# elflet.net
KiCad netlist of a schematic drawn in EAGLE
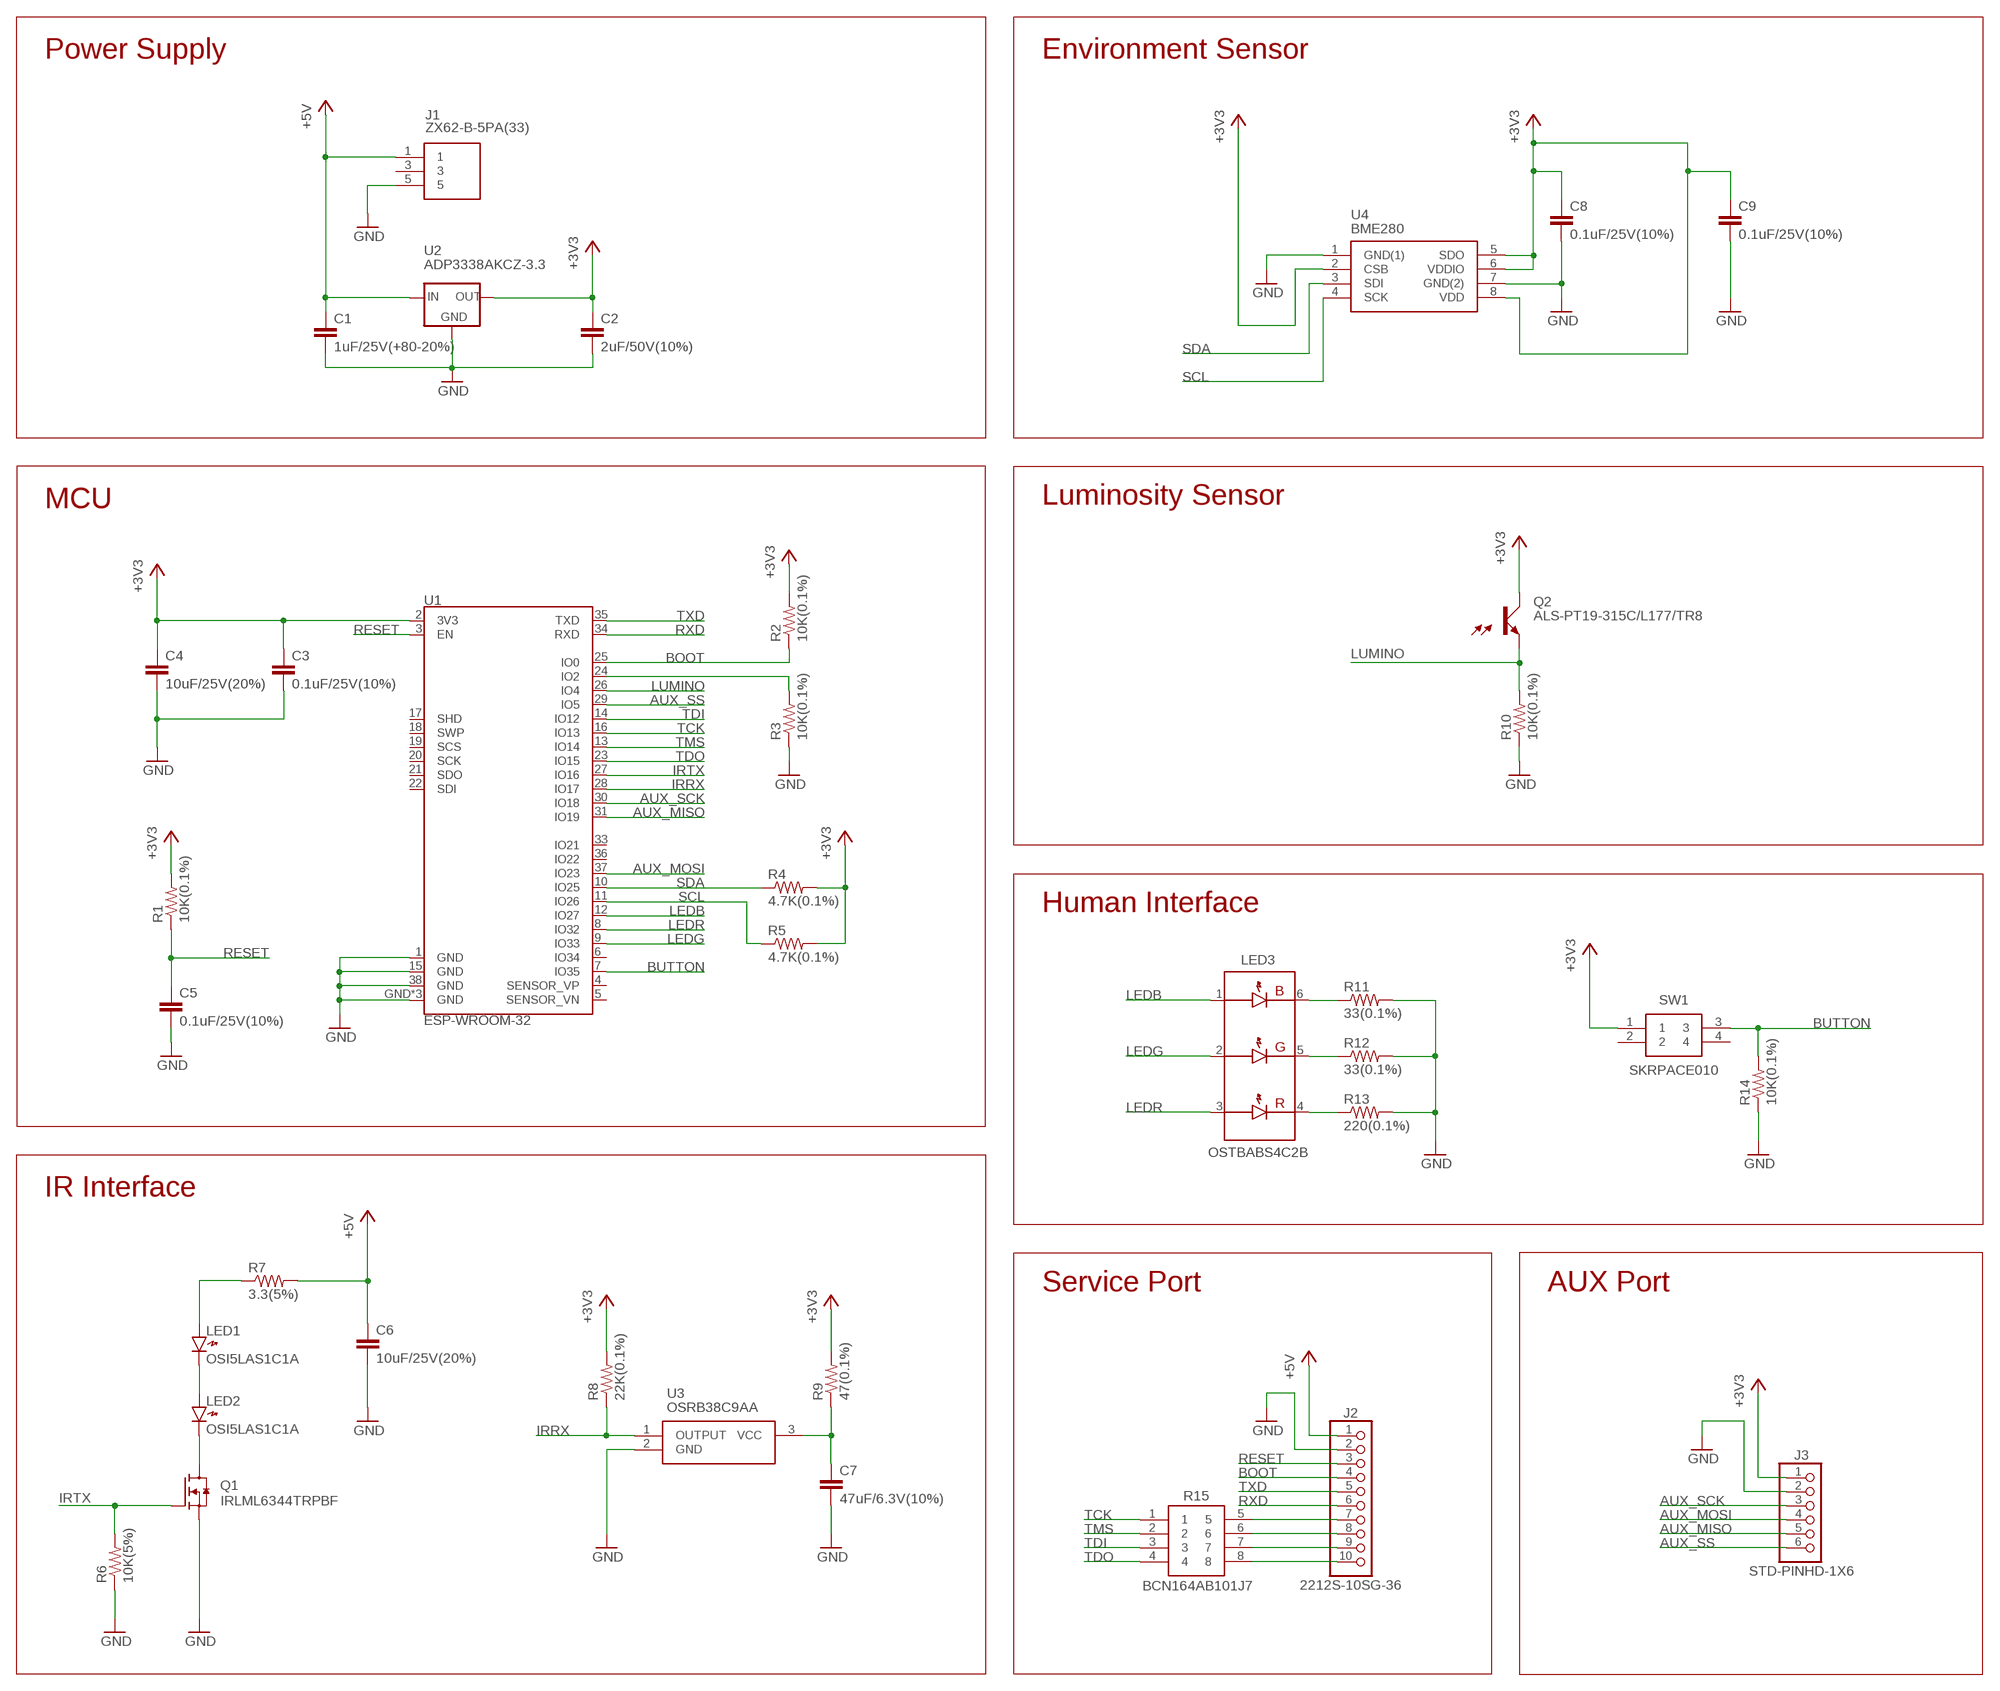
[diagram p0: schematic, sheet 1]

(export (version "E")
  (design (tool "Eeschema 10.0.6"))
  (components
    (comp (ref "C1")
      (value "1uF/25V(+80-20%)")
      (footprint "eagle-import:C3216")
      (libsource (lib "eagle-import") (part "C-EUC3216"))
    )
    (comp (ref "C2")
      (value "2uF/50V(10%)")
      (footprint "eagle-import:C3216")
      (libsource (lib "eagle-import") (part "C-EUC3216"))
    )
    (comp (ref "C3")
      (value "0.1uF/25V(10%)")
      (footprint "eagle-import:C1608")
      (libsource (lib "eagle-import") (part "C-EUC1608"))
    )
    (comp (ref "C4")
      (value "10uF/25V(20%)")
      (footprint "eagle-import:C1608")
      (libsource (lib "eagle-import") (part "C-EUC1608"))
    )
    (comp (ref "C5")
      (value "0.1uF/25V(10%)")
      (footprint "eagle-import:C1608")
      (libsource (lib "eagle-import") (part "C-EUC1608"))
    )
    (comp (ref "C6")
      (value "10uF/25V(20%)")
      (footprint "eagle-import:C1608")
      (libsource (lib "eagle-import") (part "C-EUC1608"))
    )
    (comp (ref "C7")
      (value "47uF/6.3V(10%)")
      (footprint "eagle-import:C3216")
      (libsource (lib "eagle-import") (part "C-EUC3216"))
    )
    (comp (ref "C8")
      (value "0.1uF/25V(10%)")
      (footprint "eagle-import:C1608")
      (libsource (lib "eagle-import") (part "C-EUC1608"))
    )
    (comp (ref "C9")
      (value "0.1uF/25V(10%)")
      (footprint "eagle-import:C1608")
      (libsource (lib "eagle-import") (part "C-EUC1608"))
    )
    (comp (ref "J1")
      (value "ZX62-B-5PA(33)")
      (footprint "eagle-import:ZX62-B-5PA(33)-TRUE-HANDSOLD")
      (libsource (lib "eagle-import") (part "ZX62-B-5PA(33)"))
    )
    (comp (ref "J2")
      (value "2212S-10SG-36")
      (footprint "eagle-import:STD-1X10")
      (libsource (lib "eagle-import") (part "STD-PINHD-1X10"))
    )
    (comp (ref "J3")
      (value "STD-PINHD-1X6")
      (footprint "eagle-import:STD-1X6")
      (libsource (lib "eagle-import") (part "STD-PINHD-1X6"))
    )
    (comp (ref "LED1")
      (value "OSI5LAS1C1A")
      (footprint "eagle-import:PLCC-2")
      (libsource (lib "eagle-import") (part "LEDPLCC-2"))
    )
    (comp (ref "LED2")
      (value "OSI5LAS1C1A")
      (footprint "eagle-import:PLCC-2")
      (libsource (lib "eagle-import") (part "LEDPLCC-2"))
    )
    (comp (ref "LED3")
      (value "OSTBABS4C2B")
      (footprint "eagle-import:OSTBABS4C2B")
      (libsource (lib "eagle-import") (part "OSTBABS4C2B"))
    )
    (comp (ref "Q1")
      (value "IRLML6344TRPBF")
      (footprint "eagle-import:SOT23")
      (libsource (lib "eagle-import") (part "IRLML6344TRPBF"))
    )
    (comp (ref "Q2")
      (value "ALS-PT19-315C/L177/TR8")
      (footprint "eagle-import:ALSPT19315CL177TR8")
      (libsource (lib "eagle-import") (part "ALS-PT19-315C_L177_TR8"))
    )
    (comp (ref "R1")
      (value "10K(0.1%)")
      (footprint "eagle-import:R0805")
      (libsource (lib "eagle-import") (part "rcl_334_R-US_R0805"))
    )
    (comp (ref "R2")
      (value "10K(0.1%)")
      (footprint "eagle-import:R0805")
      (libsource (lib "eagle-import") (part "rcl_334_R-US_R0805"))
    )
    (comp (ref "R3")
      (value "10K(0.1%)")
      (footprint "eagle-import:R0805")
      (libsource (lib "eagle-import") (part "rcl_334_R-US_R0805"))
    )
    (comp (ref "R4")
      (value "4.7K(0.1%)")
      (footprint "eagle-import:R0603")
      (libsource (lib "eagle-import") (part "rcl_334_R-US_R0603"))
    )
    (comp (ref "R5")
      (value "4.7K(0.1%)")
      (footprint "eagle-import:R0603")
      (libsource (lib "eagle-import") (part "rcl_334_R-US_R0603"))
    )
    (comp (ref "R6")
      (value "10K(5%)")
      (footprint "eagle-import:R0805")
      (libsource (lib "eagle-import") (part "rcl_334_R-US_R0805"))
    )
    (comp (ref "R7")
      (value "3.3(5%)")
      (footprint "eagle-import:R2512")
      (libsource (lib "eagle-import") (part "R-US_R2512"))
    )
    (comp (ref "R8")
      (value "22K(0.1%)")
      (footprint "eagle-import:R0603")
      (libsource (lib "eagle-import") (part "rcl_334_R-US_R0603"))
    )
    (comp (ref "R9")
      (value "47(0.1%)")
      (footprint "eagle-import:R0603")
      (libsource (lib "eagle-import") (part "rcl_334_R-US_R0603"))
    )
    (comp (ref "R10")
      (value "10K(0.1%)")
      (footprint "eagle-import:R0805")
      (libsource (lib "eagle-import") (part "rcl_334_R-US_R0805"))
    )
    (comp (ref "R11")
      (value "33(0.1%)")
      (footprint "eagle-import:R0805")
      (libsource (lib "eagle-import") (part "rcl_334_R-US_R0805"))
    )
    (comp (ref "R12")
      (value "33(0.1%)")
      (footprint "eagle-import:R0805")
      (libsource (lib "eagle-import") (part "rcl_334_R-US_R0805"))
    )
    (comp (ref "R13")
      (value "220(0.1%)")
      (footprint "eagle-import:R0805")
      (libsource (lib "eagle-import") (part "rcl_334_R-US_R0805"))
    )
    (comp (ref "R14")
      (value "10K(0.1%)")
      (footprint "eagle-import:R0805")
      (libsource (lib "eagle-import") (part "rcl_334_R-US_R0805"))
    )
    (comp (ref "R15")
      (value "BCN164AB101J7")
      (footprint "eagle-import:BCN164A_1")
      (fields (field (name "ARROW_PART_NUMBER") "BCN164A102J7"))
      (libsource (lib "eagle-import") (part "BCN164A102J7"))
    )
    (comp (ref "SW1")
      (value "SKRPACE010")
      (footprint "eagle-import:SMT(4.2X3.2)")
      (libsource (lib "eagle-import") (part "SKRPACE010"))
    )
    (comp (ref "U1")
      (value "ESP-WROOM-32")
      (footprint "eagle-import:ESP-WROOM-03")
      (libsource (lib "eagle-import") (part "ESP-WROOM-03"))
    )
    (comp (ref "U2")
      (value "ADP3338AKCZ-3.3")
      (footprint "eagle-import:SOT223")
      (libsource (lib "eagle-import") (part "ADP3338"))
    )
    (comp (ref "U3")
      (value "OSRB38C9AA")
      (footprint "eagle-import:OSRB38C9AA-ALT")
      (libsource (lib "eagle-import") (part "OSRB38C9AATILT"))
    )
    (comp (ref "U4")
      (value "BME280")
      (footprint "eagle-import:BME280")
      (libsource (lib "eagle-import") (part "BME280"))
    )
  )
  (nets
    (net (code "1") (name "+3V3") (class "Default")
      (node (ref "C2") (pin "1") (pinfunction "1_1") (pintype "passive"))
      (node (ref "C3") (pin "1") (pinfunction "1_1") (pintype "passive"))
      (node (ref "C4") (pin "1") (pinfunction "1_1") (pintype "passive"))
      (node (ref "C8") (pin "1") (pinfunction "1_1") (pintype "passive"))
      (node (ref "C9") (pin "1") (pinfunction "1_1") (pintype "passive"))
      (node (ref "J3") (pin "1") (pinfunction "1_1") (pintype "passive"))
      (node (ref "Q2") (pin "1") (pinfunction "C_1") (pintype "passive"))
      (node (ref "R1") (pin "2") (pinfunction "2_2") (pintype "passive"))
      (node (ref "R2") (pin "2") (pinfunction "2_2") (pintype "passive"))
      (node (ref "R4") (pin "2") (pinfunction "2_2") (pintype "passive"))
      (node (ref "R5") (pin "2") (pinfunction "2_2") (pintype "passive"))
      (node (ref "R8") (pin "2") (pinfunction "2_2") (pintype "passive"))
      (node (ref "R9") (pin "2") (pinfunction "2_2") (pintype "passive"))
      (node (ref "SW1") (pin "1") (pinfunction "1_1") (pintype "bidirectional"))
      (node (ref "U1") (pin "2") (pinfunction "3V3_2") (pintype "bidirectional"))
      (node (ref "U2") (pin "2") (pinfunction "OUT_2") (pintype "passive"))
      (node (ref "U2") (pin "4") (pinfunction "OUT_4") (pintype "passive"))
      (node (ref "U4") (pin "2") (pinfunction "CSB_2") (pintype "input"))
      (node (ref "U4") (pin "5") (pinfunction "SDO_5") (pintype "bidirectional"))
      (node (ref "U4") (pin "6") (pinfunction "VDDIO_6") (pintype "power_in"))
      (node (ref "U4") (pin "8") (pinfunction "VDD_8") (pintype "power_in"))
    )
    (net (code "2") (name "+5V") (class "Default")
      (node (ref "C1") (pin "1") (pinfunction "1_1") (pintype "passive"))
      (node (ref "C6") (pin "1") (pinfunction "1_1") (pintype "passive"))
      (node (ref "J1") (pin "1") (pinfunction "1_1") (pintype "bidirectional"))
      (node (ref "J2") (pin "1") (pinfunction "1_1") (pintype "passive"))
      (node (ref "R7") (pin "2") (pinfunction "2_2") (pintype "passive"))
      (node (ref "U2") (pin "3") (pinfunction "IN_3") (pintype "input"))
    )
    (net (code "3") (name "/AUX_MISO") (class "Default")
      (node (ref "J3") (pin "5") (pinfunction "5_5") (pintype "passive"))
      (node (ref "U1") (pin "31") (pinfunction "IO19_31") (pintype "bidirectional"))
    )
    (net (code "4") (name "/AUX_MOSI") (class "Default")
      (node (ref "J3") (pin "4") (pinfunction "4_4") (pintype "passive"))
      (node (ref "U1") (pin "37") (pinfunction "IO23_37") (pintype "bidirectional"))
    )
    (net (code "5") (name "/AUX_SCK") (class "Default")
      (node (ref "J3") (pin "3") (pinfunction "3_3") (pintype "passive"))
      (node (ref "U1") (pin "30") (pinfunction "IO18_30") (pintype "bidirectional"))
    )
    (net (code "6") (name "/AUX_SS") (class "Default")
      (node (ref "J3") (pin "6") (pinfunction "6_6") (pintype "passive"))
      (node (ref "U1") (pin "29") (pinfunction "IO5_29") (pintype "bidirectional"))
    )
    (net (code "7") (name "/BOOT") (class "Default")
      (node (ref "J2") (pin "4") (pinfunction "4_4") (pintype "passive"))
      (node (ref "R2") (pin "1") (pinfunction "1_1") (pintype "passive"))
      (node (ref "U1") (pin "25") (pinfunction "IO0_25") (pintype "bidirectional"))
    )
    (net (code "8") (name "/BUTTON") (class "Default")
      (node (ref "R14") (pin "2") (pinfunction "2_2") (pintype "passive"))
      (node (ref "SW1") (pin "3") (pinfunction "3_3") (pintype "bidirectional"))
      (node (ref "U1") (pin "7") (pinfunction "IO35_7") (pintype "bidirectional"))
    )
    (net (code "9") (name "/IRRX") (class "Default")
      (node (ref "R8") (pin "1") (pinfunction "1_1") (pintype "passive"))
      (node (ref "U1") (pin "28") (pinfunction "IO17_28") (pintype "bidirectional"))
      (node (ref "U3") (pin "1") (pinfunction "OUTPUT_1") (pintype "bidirectional"))
    )
    (net (code "10") (name "/IRTX") (class "Default")
      (node (ref "Q1") (pin "1") (pinfunction "G_1") (pintype "passive"))
      (node (ref "R6") (pin "2") (pinfunction "2_2") (pintype "passive"))
      (node (ref "U1") (pin "27") (pinfunction "IO16_27") (pintype "bidirectional"))
    )
    (net (code "11") (name "/LEDB") (class "Default")
      (node (ref "LED3") (pin "1") (pinfunction "AB_1") (pintype "passive"))
      (node (ref "U1") (pin "12") (pinfunction "IO27_12") (pintype "bidirectional"))
    )
    (net (code "12") (name "/LEDG") (class "Default")
      (node (ref "LED3") (pin "2") (pinfunction "AG_2") (pintype "passive"))
      (node (ref "U1") (pin "9") (pinfunction "IO33_9") (pintype "bidirectional"))
    )
    (net (code "13") (name "/LEDR") (class "Default")
      (node (ref "LED3") (pin "3") (pinfunction "AR_3") (pintype "passive"))
      (node (ref "U1") (pin "8") (pinfunction "IO32_8") (pintype "bidirectional"))
    )
    (net (code "14") (name "/LUMINO") (class "Default")
      (node (ref "Q2") (pin "2") (pinfunction "E_2") (pintype "passive"))
      (node (ref "R10") (pin "2") (pinfunction "2_2") (pintype "passive"))
      (node (ref "U1") (pin "26") (pinfunction "IO4_26") (pintype "bidirectional"))
    )
    (net (code "15") (name "/RESET") (class "Default")
      (node (ref "C5") (pin "1") (pinfunction "1_1") (pintype "passive"))
      (node (ref "J2") (pin "3") (pinfunction "3_3") (pintype "passive"))
      (node (ref "R1") (pin "1") (pinfunction "1_1") (pintype "passive"))
      (node (ref "U1") (pin "3") (pinfunction "EN_3") (pintype "bidirectional"))
    )
    (net (code "16") (name "/RXD") (class "Default")
      (node (ref "J2") (pin "6") (pinfunction "6_6") (pintype "passive"))
      (node (ref "U1") (pin "34") (pinfunction "RXD_34") (pintype "bidirectional"))
    )
    (net (code "17") (name "/SCL") (class "Default")
      (node (ref "R5") (pin "1") (pinfunction "1_1") (pintype "passive"))
      (node (ref "U1") (pin "11") (pinfunction "IO26_11") (pintype "bidirectional"))
      (node (ref "U4") (pin "4") (pinfunction "SCK_4") (pintype "bidirectional"))
    )
    (net (code "18") (name "/SDA") (class "Default")
      (node (ref "R4") (pin "1") (pinfunction "1_1") (pintype "passive"))
      (node (ref "U1") (pin "10") (pinfunction "IO25_10") (pintype "bidirectional"))
      (node (ref "U4") (pin "3") (pinfunction "SDI_3") (pintype "bidirectional"))
    )
    (net (code "19") (name "/TCK") (class "Default")
      (node (ref "R15") (pin "1") (pinfunction "1_1") (pintype "bidirectional"))
      (node (ref "U1") (pin "16") (pinfunction "IO13_16") (pintype "bidirectional"))
    )
    (net (code "20") (name "/TDI") (class "Default")
      (node (ref "R15") (pin "3") (pinfunction "3_3") (pintype "bidirectional"))
      (node (ref "U1") (pin "14") (pinfunction "IO12_14") (pintype "bidirectional"))
    )
    (net (code "21") (name "/TDO") (class "Default")
      (node (ref "R15") (pin "4") (pinfunction "4_4") (pintype "bidirectional"))
      (node (ref "U1") (pin "23") (pinfunction "IO15_23") (pintype "bidirectional"))
    )
    (net (code "22") (name "/TMS") (class "Default")
      (node (ref "R15") (pin "2") (pinfunction "2_2") (pintype "bidirectional"))
      (node (ref "U1") (pin "13") (pinfunction "IO14_13") (pintype "bidirectional"))
    )
    (net (code "23") (name "/TXD") (class "Default")
      (node (ref "J2") (pin "5") (pinfunction "5_5") (pintype "passive"))
      (node (ref "U1") (pin "35") (pinfunction "TXD_35") (pintype "bidirectional"))
    )
    (net (code "24") (name "GND") (class "Default")
      (node (ref "C1") (pin "2") (pinfunction "2_2") (pintype "passive"))
      (node (ref "C2") (pin "2") (pinfunction "2_2") (pintype "passive"))
      (node (ref "C3") (pin "2") (pinfunction "2_2") (pintype "passive"))
      (node (ref "C4") (pin "2") (pinfunction "2_2") (pintype "passive"))
      (node (ref "C5") (pin "2") (pinfunction "2_2") (pintype "passive"))
      (node (ref "C6") (pin "2") (pinfunction "2_2") (pintype "passive"))
      (node (ref "C7") (pin "2") (pinfunction "2_2") (pintype "passive"))
      (node (ref "C8") (pin "2") (pinfunction "2_2") (pintype "passive"))
      (node (ref "C9") (pin "2") (pinfunction "2_2") (pintype "passive"))
      (node (ref "J1") (pin "5") (pinfunction "5_5") (pintype "bidirectional"))
      (node (ref "J2") (pin "2") (pinfunction "2_2") (pintype "passive"))
      (node (ref "J3") (pin "2") (pinfunction "2_2") (pintype "passive"))
      (node (ref "Q1") (pin "2") (pinfunction "S_2") (pintype "passive"))
      (node (ref "R10") (pin "1") (pinfunction "1_1") (pintype "passive"))
      (node (ref "R11") (pin "2") (pinfunction "2_2") (pintype "passive"))
      (node (ref "R12") (pin "2") (pinfunction "2_2") (pintype "passive"))
      (node (ref "R13") (pin "2") (pinfunction "2_2") (pintype "passive"))
      (node (ref "R14") (pin "1") (pinfunction "1_1") (pintype "passive"))
      (node (ref "R3") (pin "1") (pinfunction "1_1") (pintype "passive"))
      (node (ref "R6") (pin "1") (pinfunction "1_1") (pintype "passive"))
      (node (ref "U1") (pin "1") (pinfunction "GND_1") (pintype "bidirectional"))
      (node (ref "U1") (pin "15") (pinfunction "GND_15") (pintype "bidirectional"))
      (node (ref "U1") (pin "38") (pinfunction "GND_38") (pintype "bidirectional"))
      (node (ref "U1") (pin "GND") (pinfunction "GND_GND") (pintype "bidirectional"))
      (node (ref "U1") (pin "GND_B") (pinfunction "GND_GND_B") (pintype "bidirectional"))
      (node (ref "U1") (pin "GND_V") (pinfunction "GND_GND_V") (pintype "bidirectional"))
      (node (ref "U2") (pin "1") (pinfunction "GND_1") (pintype "input"))
      (node (ref "U3") (pin "2") (pinfunction "GND_2") (pintype "bidirectional"))
      (node (ref "U4") (pin "1") (pinfunction "GND(1)_1") (pintype "power_in"))
      (node (ref "U4") (pin "7") (pinfunction "GND(2)_7") (pintype "power_in"))
    )
    (net (code "25") (name "Net-(J2-Pad7)") (class "Default")
      (node (ref "J2") (pin "7") (pinfunction "7_7") (pintype "passive"))
      (node (ref "R15") (pin "5") (pinfunction "5_5") (pintype "bidirectional"))
    )
    (net (code "26") (name "Net-(J2-Pad8)") (class "Default")
      (node (ref "J2") (pin "8") (pinfunction "8_8") (pintype "passive"))
      (node (ref "R15") (pin "6") (pinfunction "6_6") (pintype "bidirectional"))
    )
    (net (code "27") (name "Net-(J2-Pad9)") (class "Default")
      (node (ref "J2") (pin "9") (pinfunction "9_9") (pintype "passive"))
      (node (ref "R15") (pin "7") (pinfunction "7_7") (pintype "bidirectional"))
    )
    (net (code "28") (name "Net-(J2-Pad10)") (class "Default")
      (node (ref "J2") (pin "10") (pinfunction "10_10") (pintype "passive"))
      (node (ref "R15") (pin "8") (pinfunction "8_8") (pintype "bidirectional"))
    )
    (net (code "29") (name "Net-(LED1-A)") (class "Default")
      (node (ref "LED1") (pin "2") (pinfunction "A_2") (pintype "passive"))
      (node (ref "R7") (pin "1") (pinfunction "1_1") (pintype "passive"))
    )
    (net (code "30") (name "Net-(LED1-K)") (class "Default")
      (node (ref "LED1") (pin "1") (pinfunction "K_1") (pintype "passive"))
      (node (ref "LED2") (pin "2") (pinfunction "A_2") (pintype "passive"))
    )
    (net (code "31") (name "Net-(LED2-K)") (class "Default")
      (node (ref "LED2") (pin "1") (pinfunction "K_1") (pintype "passive"))
      (node (ref "Q1") (pin "3") (pinfunction "D_3") (pintype "passive"))
    )
    (net (code "32") (name "Net-(LED3-KB)") (class "Default")
      (node (ref "LED3") (pin "6") (pinfunction "KB_6") (pintype "passive"))
      (node (ref "R11") (pin "1") (pinfunction "1_1") (pintype "passive"))
    )
    (net (code "33") (name "Net-(LED3-KG)") (class "Default")
      (node (ref "LED3") (pin "5") (pinfunction "KG_5") (pintype "passive"))
      (node (ref "R12") (pin "1") (pinfunction "1_1") (pintype "passive"))
    )
    (net (code "34") (name "Net-(LED3-KR)") (class "Default")
      (node (ref "LED3") (pin "4") (pinfunction "KR_4") (pintype "passive"))
      (node (ref "R13") (pin "1") (pinfunction "1_1") (pintype "passive"))
    )
    (net (code "35") (name "Net-(U1-IO2)") (class "Default")
      (node (ref "R3") (pin "2") (pinfunction "2_2") (pintype "passive"))
      (node (ref "U1") (pin "24") (pinfunction "IO2_24") (pintype "bidirectional"))
    )
    (net (code "36") (name "Net-(U3-VCC)") (class "Default")
      (node (ref "C7") (pin "1") (pinfunction "1_1") (pintype "passive"))
      (node (ref "R9") (pin "1") (pinfunction "1_1") (pintype "passive"))
      (node (ref "U3") (pin "3") (pinfunction "VCC_3") (pintype "bidirectional"))
    )
    (net (code "37") (name "unconnected-(J1-Pad3)") (class "Default")
      (node (ref "J1") (pin "3") (pinfunction "3_3") (pintype "bidirectional"))
    )
    (net (code "38") (name "unconnected-(SW1-Pad2)") (class "Default")
      (node (ref "SW1") (pin "2") (pinfunction "2_2") (pintype "bidirectional"))
    )
    (net (code "39") (name "unconnected-(SW1-Pad4)") (class "Default")
      (node (ref "SW1") (pin "4") (pinfunction "4_4") (pintype "bidirectional"))
    )
    (net (code "40") (name "unconnected-(U1-IO21-Pad33)") (class "Default")
      (node (ref "U1") (pin "33") (pinfunction "IO21_33") (pintype "bidirectional"))
    )
    (net (code "41") (name "unconnected-(U1-IO22-Pad36)") (class "Default")
      (node (ref "U1") (pin "36") (pinfunction "IO22_36") (pintype "bidirectional"))
    )
    (net (code "42") (name "unconnected-(U1-IO34-Pad6)") (class "Default")
      (node (ref "U1") (pin "6") (pinfunction "IO34_6") (pintype "bidirectional"))
    )
    (net (code "43") (name "unconnected-(U1-SCK-Pad20)") (class "Default")
      (node (ref "U1") (pin "20") (pinfunction "SCK_20") (pintype "bidirectional"))
    )
    (net (code "44") (name "unconnected-(U1-SCS-Pad19)") (class "Default")
      (node (ref "U1") (pin "19") (pinfunction "SCS_19") (pintype "bidirectional"))
    )
    (net (code "45") (name "unconnected-(U1-SDI-Pad22)") (class "Default")
      (node (ref "U1") (pin "22") (pinfunction "SDI_22") (pintype "bidirectional"))
    )
    (net (code "46") (name "unconnected-(U1-SDO-Pad21)") (class "Default")
      (node (ref "U1") (pin "21") (pinfunction "SDO_21") (pintype "bidirectional"))
    )
    (net (code "47") (name "unconnected-(U1-SENSOR_VN-Pad5)") (class "Default")
      (node (ref "U1") (pin "5") (pinfunction "SENSOR_VN_5") (pintype "bidirectional"))
    )
    (net (code "48") (name "unconnected-(U1-SENSOR_VP-Pad4)") (class "Default")
      (node (ref "U1") (pin "4") (pinfunction "SENSOR_VP_4") (pintype "bidirectional"))
    )
    (net (code "49") (name "unconnected-(U1-SHD-Pad17)") (class "Default")
      (node (ref "U1") (pin "17") (pinfunction "SHD_17") (pintype "bidirectional"))
    )
    (net (code "50") (name "unconnected-(U1-SWP-Pad18)") (class "Default")
      (node (ref "U1") (pin "18") (pinfunction "SWP_18") (pintype "bidirectional"))
    )
  )
)
